# Voltage_Regulator_and_Level_Shifters.net
KiCad netlist of a schematic drawn in Altium Designer
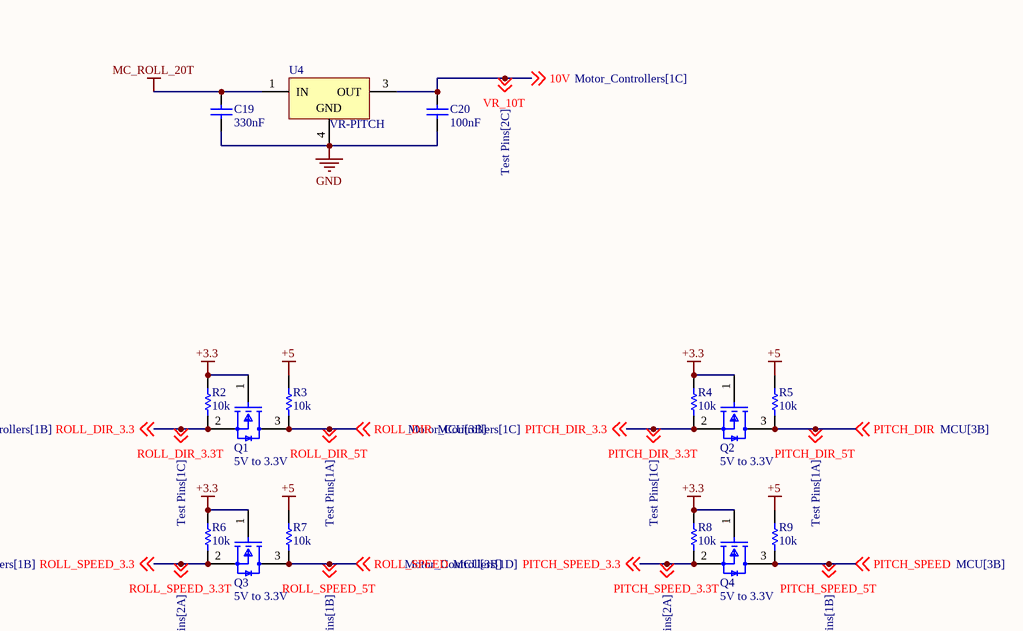
[diagram p0: Voltage_Regulator and Level Shifters.SchDoc]

(export (version "E")
  (design (tool "Eeschema 10.0.6"))
  (components
    (comp (ref "C19")
      (value "330nF")
      (footprint "0805")
      (description "CAP Ceramic, 330nF, 50V, 0805")
      (fields (field (name "MPN") "0805B334K500NT") (field (name "JLCPCB PART #") "C1740"))
      (libsource (lib "JLCPCB Ceramic Capacitor Schematic Lib") (part "nF - 330nF (0.33uF)"))
    )
    (comp (ref "C20")
      (value "100nF")
      (footprint "0805")
      (description "CAP Ceramic, 100nF, 50V, 0805")
      (fields (field (name "MPN") "CC0805KRX7R9BB104") (field (name "JLCPCB PART #") "C49678"))
      (libsource (lib "JLCPCB Ceramic Capacitor Schematic Lib") (part "nF - 100nF (0.1uF)"))
    )
    (comp (ref "Q1")
      (value "5V to 3.3V")
      (footprint "FP-318-08-IPC_B")
      (description "MOSFET N-CH 50V 220MA SOT-23")
      (fields (field (name "MPN") "BSS138"))
      (libsource (lib "Altium Content Vault") (part "3b9c635fedb024a5347a57b145af9cc"))
    )
    (comp (ref "Q2")
      (value "5V to 3.3V")
      (footprint "FP-318-08-IPC_B")
      (description "MOSFET N-CH 50V 220MA SOT-23")
      (fields (field (name "MPN") "BSS138"))
      (libsource (lib "Altium Content Vault") (part "3b9c635fedb024a5347a57b145af9cc"))
    )
    (comp (ref "Q3")
      (value "5V to 3.3V")
      (footprint "FP-318-08-IPC_B")
      (description "MOSFET N-CH 50V 220MA SOT-23")
      (fields (field (name "MPN") "BSS138"))
      (libsource (lib "Altium Content Vault") (part "3b9c635fedb024a5347a57b145af9cc"))
    )
    (comp (ref "Q4")
      (value "5V to 3.3V")
      (footprint "FP-318-08-IPC_B")
      (description "MOSFET N-CH 50V 220MA SOT-23")
      (fields (field (name "MPN") "BSS138"))
      (libsource (lib "Altium Content Vault") (part "3b9c635fedb024a5347a57b145af9cc"))
    )
    (comp (ref "R2")
      (value "10k")
      (footprint "0805")
      (description "RES Thick Film, 10kΩ, 0.125W, 150V, 0805")
      (fields (field (name "MPN") "0805W8F1002T5E") (field (name "JLCPCB PART #") "C17414"))
      (libsource (lib "JLCPCB Resistor Schematic Lib") (part "10000 (10k)"))
    )
    (comp (ref "R3")
      (value "10k")
      (footprint "0805")
      (description "RES Thick Film, 10kΩ, 0.125W, 150V, 0805")
      (fields (field (name "MPN") "0805W8F1002T5E") (field (name "JLCPCB PART #") "C17414"))
      (libsource (lib "JLCPCB Resistor Schematic Lib") (part "10000 (10k)"))
    )
    (comp (ref "R4")
      (value "10k")
      (footprint "0805")
      (description "RES Thick Film, 10kΩ, 0.125W, 150V, 0805")
      (fields (field (name "MPN") "0805W8F1002T5E") (field (name "JLCPCB PART #") "C17414"))
      (libsource (lib "JLCPCB Resistor Schematic Lib") (part "10000 (10k)"))
    )
    (comp (ref "R5")
      (value "10k")
      (footprint "0805")
      (description "RES Thick Film, 10kΩ, 0.125W, 150V, 0805")
      (fields (field (name "MPN") "0805W8F1002T5E") (field (name "JLCPCB PART #") "C17414"))
      (libsource (lib "JLCPCB Resistor Schematic Lib") (part "10000 (10k)"))
    )
    (comp (ref "R6")
      (value "10k")
      (footprint "0805")
      (description "RES Thick Film, 10kΩ, 0.125W, 150V, 0805")
      (fields (field (name "MPN") "0805W8F1002T5E") (field (name "JLCPCB PART #") "C17414"))
      (libsource (lib "JLCPCB Resistor Schematic Lib") (part "10000 (10k)"))
    )
    (comp (ref "R7")
      (value "10k")
      (footprint "0805")
      (description "RES Thick Film, 10kΩ, 0.125W, 150V, 0805")
      (fields (field (name "MPN") "0805W8F1002T5E") (field (name "JLCPCB PART #") "C17414"))
      (libsource (lib "JLCPCB Resistor Schematic Lib") (part "10000 (10k)"))
    )
    (comp (ref "R8")
      (value "10k")
      (footprint "0805")
      (description "RES Thick Film, 10kΩ, 0.125W, 150V, 0805")
      (fields (field (name "MPN") "0805W8F1002T5E") (field (name "JLCPCB PART #") "C17414"))
      (libsource (lib "JLCPCB Resistor Schematic Lib") (part "10000 (10k)"))
    )
    (comp (ref "R9")
      (value "10k")
      (footprint "0805")
      (description "RES Thick Film, 10kΩ, 0.125W, 150V, 0805")
      (fields (field (name "MPN") "0805W8F1002T5E") (field (name "JLCPCB PART #") "C17414"))
      (libsource (lib "JLCPCB Resistor Schematic Lib") (part "10000 (10k)"))
    )
    (comp (ref "U4")
      (value "VR-PITCH")
      (footprint "TO-263_N")
      (description "Positive Voltage Regulator, 3-Pin D2PAK, Tape and Reel")
      (libsource (lib "l7812") (part "CMP-0244-00182-1"))
    )
  )
  (nets
    (net (code "1") (name "+3.3") (class "Default")
      (node (ref "Q1") (pin "1") (pinfunction "G_1") (pintype "passive"))
      (node (ref "Q2") (pin "1") (pinfunction "G_1") (pintype "passive"))
      (node (ref "Q3") (pin "1") (pinfunction "G_1") (pintype "passive"))
      (node (ref "Q4") (pin "1") (pinfunction "G_1") (pintype "passive"))
      (node (ref "R2") (pin "2") (pinfunction "2_2") (pintype "passive"))
      (node (ref "R4") (pin "2") (pinfunction "2_2") (pintype "passive"))
      (node (ref "R6") (pin "2") (pinfunction "2_2") (pintype "passive"))
      (node (ref "R8") (pin "2") (pinfunction "2_2") (pintype "passive"))
    )
    (net (code "2") (name "+5") (class "Default")
      (node (ref "R3") (pin "2") (pinfunction "2_2") (pintype "passive"))
      (node (ref "R5") (pin "2") (pinfunction "2_2") (pintype "passive"))
      (node (ref "R7") (pin "2") (pinfunction "2_2") (pintype "passive"))
      (node (ref "R9") (pin "2") (pinfunction "2_2") (pintype "passive"))
    )
    (net (code "3") (name "10V") (class "Default")
      (node (ref "C20") (pin "1") (pinfunction "1_1") (pintype "passive"))
      (node (ref "U4") (pin "3") (pinfunction "OUT_3") (pintype "power_in"))
    )
    (net (code "4") (name "GND") (class "Default")
      (node (ref "C19") (pin "1") (pinfunction "1_1") (pintype "passive"))
      (node (ref "C20") (pin "2") (pinfunction "2_2") (pintype "passive"))
      (node (ref "U4") (pin "4") (pinfunction "GND_4") (pintype "power_in"))
    )
    (net (code "5") (name "MC_ROLL_20T") (class "Default")
      (node (ref "C19") (pin "2") (pinfunction "2_2") (pintype "passive"))
      (node (ref "U4") (pin "1") (pinfunction "IN_1") (pintype "power_in"))
    )
    (net (code "6") (name "PITCH_DIR") (class "Default")
      (node (ref "Q2") (pin "3") (pinfunction "D_3") (pintype "passive"))
      (node (ref "R5") (pin "1") (pinfunction "1_1") (pintype "passive"))
    )
    (net (code "7") (name "PITCH_DIR_3.3") (class "Default")
      (node (ref "Q2") (pin "2") (pinfunction "S_2") (pintype "passive"))
      (node (ref "R4") (pin "1") (pinfunction "1_1") (pintype "passive"))
    )
    (net (code "8") (name "PITCH_SPEED") (class "Default")
      (node (ref "Q4") (pin "3") (pinfunction "D_3") (pintype "passive"))
      (node (ref "R9") (pin "1") (pinfunction "1_1") (pintype "passive"))
    )
    (net (code "9") (name "PITCH_SPEED_3.3") (class "Default")
      (node (ref "Q4") (pin "2") (pinfunction "S_2") (pintype "passive"))
      (node (ref "R8") (pin "1") (pinfunction "1_1") (pintype "passive"))
    )
    (net (code "10") (name "ROLL_DIR") (class "Default")
      (node (ref "Q1") (pin "3") (pinfunction "D_3") (pintype "passive"))
      (node (ref "R3") (pin "1") (pinfunction "1_1") (pintype "passive"))
    )
    (net (code "11") (name "ROLL_DIR_3.3") (class "Default")
      (node (ref "Q1") (pin "2") (pinfunction "S_2") (pintype "passive"))
      (node (ref "R2") (pin "1") (pinfunction "1_1") (pintype "passive"))
    )
    (net (code "12") (name "ROLL_SPEED") (class "Default")
      (node (ref "Q3") (pin "3") (pinfunction "D_3") (pintype "passive"))
      (node (ref "R7") (pin "1") (pinfunction "1_1") (pintype "passive"))
    )
    (net (code "13") (name "ROLL_SPEED_3.3") (class "Default")
      (node (ref "Q3") (pin "2") (pinfunction "S_2") (pintype "passive"))
      (node (ref "R6") (pin "1") (pinfunction "1_1") (pintype "passive"))
    )
  )
)
